# DS18B20.net
KiCad netlist of a schematic drawn in Altium Designer
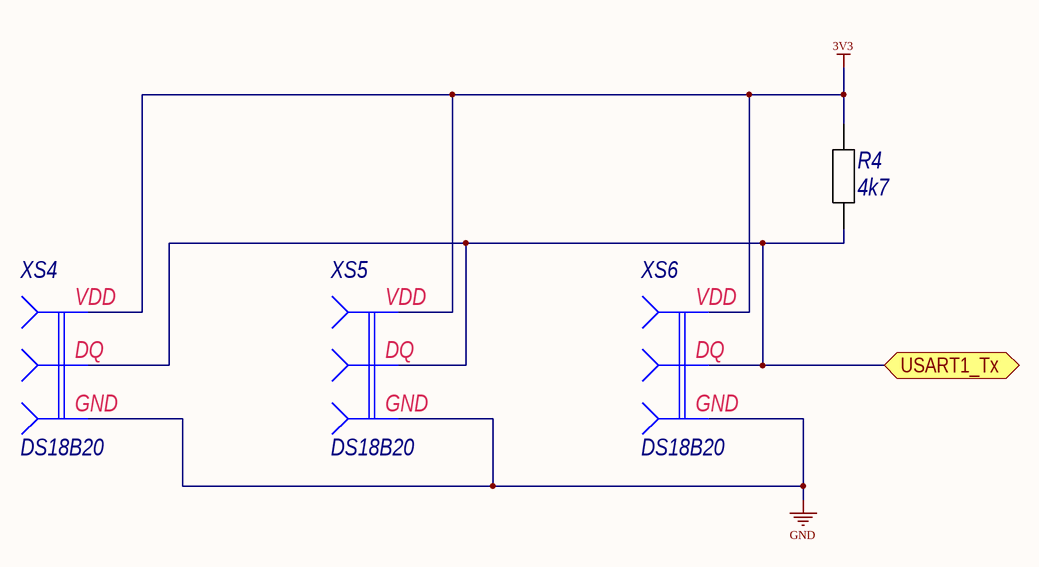
[diagram p0: DS18B20.SchDoc]

(export (version "E")
  (design (tool "Eeschema 10.0.6"))
  (components
    (comp (ref "R4")
      (value "4k7")
      (footprint "C0805R")
      (fields (field (name "PUBLISHER") "Andrew Danich"))
      (libsource (lib "PA_control_board") (part "R0805"))
    )
    (comp (ref "XS4")
      (value "DS18B20")
      (footprint "YX-XH-3")
      (fields (field (name "PUBLISHER") "Andrew Danich"))
      (libsource (lib "PA_control_board") (part "DS18B20"))
    )
    (comp (ref "XS5")
      (value "DS18B20")
      (footprint "YX-XH-3")
      (fields (field (name "PUBLISHER") "Andrew Danich"))
      (libsource (lib "PA_control_board") (part "DS18B20"))
    )
    (comp (ref "XS6")
      (value "DS18B20")
      (footprint "YX-XH-3")
      (fields (field (name "PUBLISHER") "Andrew Danich"))
      (libsource (lib "PA_control_board") (part "DS18B20"))
    )
  )
  (nets
    (net (code "1") (name "/USART1_Tx") (class "Default")
      (node (ref "R4") (pin "2") (pinfunction "2_2") (pintype "passive"))
      (node (ref "XS4") (pin "2") (pintype "passive"))
      (node (ref "XS5") (pin "2") (pintype "passive"))
      (node (ref "XS6") (pin "2") (pintype "passive"))
    )
    (net (code "2") (name "3V3") (class "Default")
      (node (ref "R4") (pin "1") (pinfunction "1_1") (pintype "passive"))
      (node (ref "XS4") (pin "1") (pintype "passive"))
      (node (ref "XS5") (pin "1") (pintype "passive"))
      (node (ref "XS6") (pin "1") (pintype "passive"))
    )
    (net (code "3") (name "GND") (class "Default")
      (node (ref "XS4") (pin "3") (pintype "passive"))
      (node (ref "XS5") (pin "3") (pintype "passive"))
      (node (ref "XS6") (pin "3") (pintype "passive"))
    )
  )
)
